# RPIcoffeeOptocouplerboard.net
KiCad netlist of a schematic drawn in EAGLE
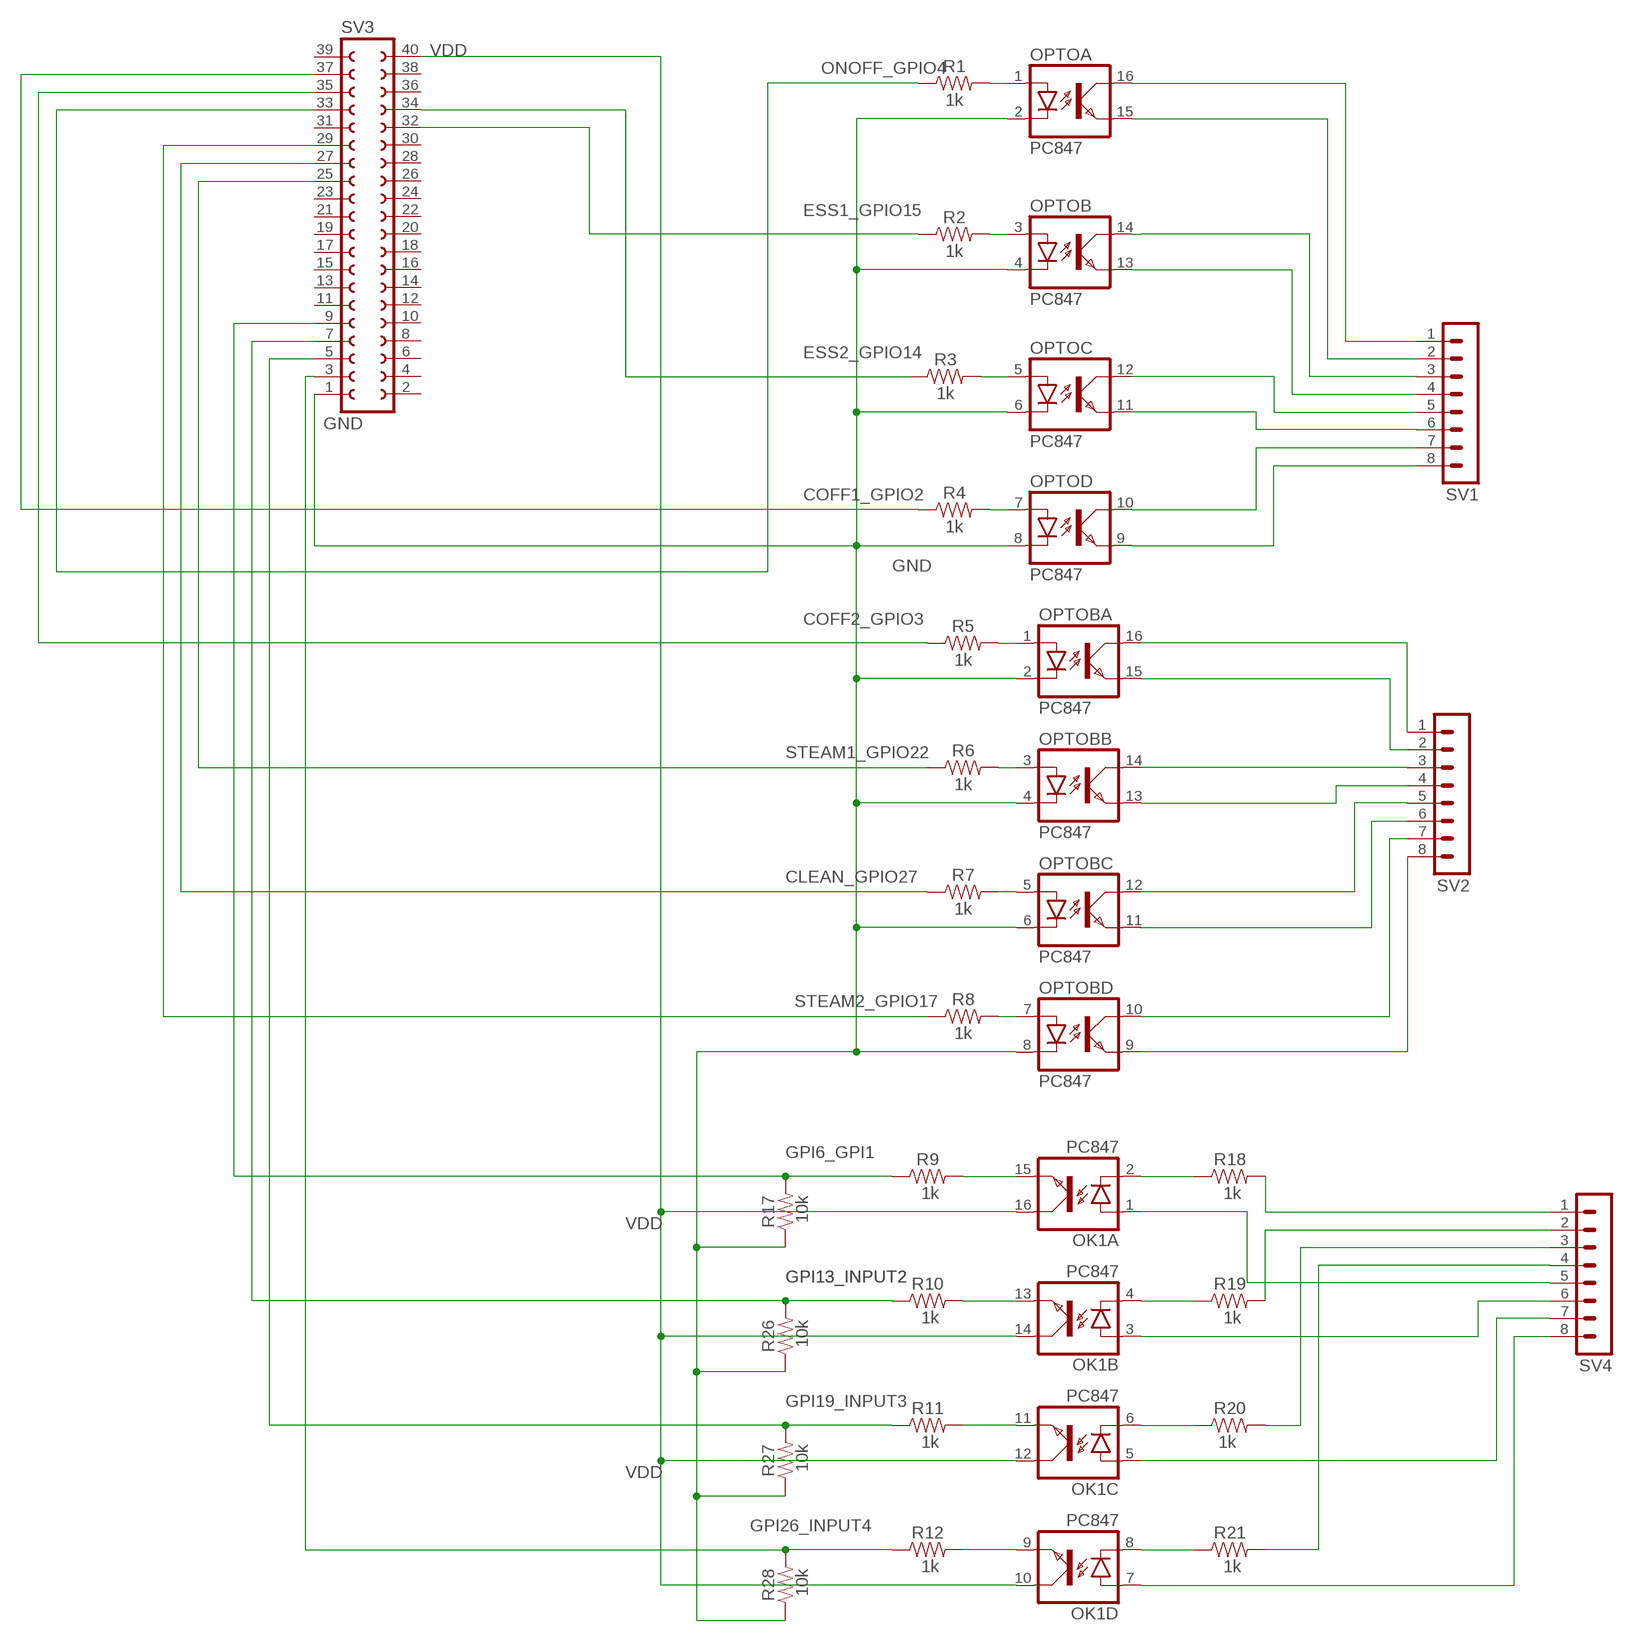
[diagram p0: schematic, sheet 1]

(export (version "E")
  (design (tool "Eeschema 10.0.6"))
  (components
    (comp (ref "OK1")
      (value "PC847")
      (footprint "eagle-import:DIL16")
      (libsource (lib "eagle-import") (part "PC847"))
    )
    (comp (ref "OPTO")
      (value "PC847")
      (footprint "eagle-import:DIL16")
      (libsource (lib "eagle-import") (part "PC847"))
    )
    (comp (ref "OPTOB")
      (value "PC847")
      (footprint "eagle-import:DIL16")
      (libsource (lib "eagle-import") (part "PC847"))
    )
    (comp (ref "R1")
      (value "1k")
      (footprint "eagle-import:AXIAL-0.3")
      (libsource (lib "eagle-import") (part "1KOHM-HORIZ-1/4W-5%"))
    )
    (comp (ref "R2")
      (value "1k")
      (footprint "eagle-import:AXIAL-0.3")
      (libsource (lib "eagle-import") (part "1KOHM-HORIZ-1/4W-5%"))
    )
    (comp (ref "R3")
      (value "1k")
      (footprint "eagle-import:AXIAL-0.3")
      (libsource (lib "eagle-import") (part "1KOHM-HORIZ-1/4W-5%"))
    )
    (comp (ref "R4")
      (value "1k")
      (footprint "eagle-import:AXIAL-0.3")
      (libsource (lib "eagle-import") (part "1KOHM-HORIZ-1/4W-5%"))
    )
    (comp (ref "R5")
      (value "1k")
      (footprint "eagle-import:AXIAL-0.3")
      (libsource (lib "eagle-import") (part "1KOHM-HORIZ-1/4W-5%"))
    )
    (comp (ref "R6")
      (value "1k")
      (footprint "eagle-import:AXIAL-0.3")
      (libsource (lib "eagle-import") (part "1KOHM-HORIZ-1/4W-5%"))
    )
    (comp (ref "R7")
      (value "1k")
      (footprint "eagle-import:AXIAL-0.3")
      (libsource (lib "eagle-import") (part "1KOHM-HORIZ-1/4W-5%"))
    )
    (comp (ref "R8")
      (value "1k")
      (footprint "eagle-import:AXIAL-0.3")
      (libsource (lib "eagle-import") (part "1KOHM-HORIZ-1/4W-5%"))
    )
    (comp (ref "R9")
      (value "1k")
      (footprint "eagle-import:AXIAL-0.3")
      (libsource (lib "eagle-import") (part "RESISTORAXIAL-0.3"))
    )
    (comp (ref "R10")
      (value "1k")
      (footprint "eagle-import:AXIAL-0.3")
      (libsource (lib "eagle-import") (part "RESISTORAXIAL-0.3"))
    )
    (comp (ref "R11")
      (value "1k")
      (footprint "eagle-import:AXIAL-0.3")
      (libsource (lib "eagle-import") (part "RESISTORAXIAL-0.3"))
    )
    (comp (ref "R12")
      (value "1k")
      (footprint "eagle-import:AXIAL-0.3")
      (libsource (lib "eagle-import") (part "RESISTORAXIAL-0.3"))
    )
    (comp (ref "R17")
      (value "10k")
      (footprint "eagle-import:AXIAL-0.3")
      (libsource (lib "eagle-import") (part "RESISTORAXIAL-0.3"))
    )
    (comp (ref "R18")
      (value "1k")
      (footprint "eagle-import:AXIAL-0.3")
      (libsource (lib "eagle-import") (part "RESISTORAXIAL-0.3"))
    )
    (comp (ref "R19")
      (value "1k")
      (footprint "eagle-import:AXIAL-0.3")
      (libsource (lib "eagle-import") (part "RESISTORAXIAL-0.3"))
    )
    (comp (ref "R20")
      (value "1k")
      (footprint "eagle-import:AXIAL-0.3")
      (libsource (lib "eagle-import") (part "RESISTORAXIAL-0.3"))
    )
    (comp (ref "R21")
      (value "1k")
      (footprint "eagle-import:AXIAL-0.3")
      (libsource (lib "eagle-import") (part "RESISTORAXIAL-0.3"))
    )
    (comp (ref "R26")
      (value "10k")
      (footprint "eagle-import:AXIAL-0.3")
      (libsource (lib "eagle-import") (part "RESISTORAXIAL-0.3"))
    )
    (comp (ref "R27")
      (value "10k")
      (footprint "eagle-import:AXIAL-0.3")
      (libsource (lib "eagle-import") (part "RESISTORAXIAL-0.3"))
    )
    (comp (ref "R28")
      (value "10k")
      (footprint "eagle-import:AXIAL-0.3")
      (libsource (lib "eagle-import") (part "RESISTORAXIAL-0.3"))
    )
    (comp (ref "SV1")
      (value "MA08-1")
      (footprint "eagle-import:MA08-1")
      (libsource (lib "eagle-import") (part "MA08-1"))
    )
    (comp (ref "SV2")
      (value "MA08-1")
      (footprint "eagle-import:MA08-1")
      (libsource (lib "eagle-import") (part "MA08-1"))
    )
    (comp (ref "SV3")
      (value "FE20-2")
      (footprint "eagle-import:FE20-2")
      (libsource (lib "eagle-import") (part "FE20-2"))
    )
    (comp (ref "SV4")
      (value "MA08-1")
      (footprint "eagle-import:MA08-1")
      (libsource (lib "eagle-import") (part "MA08-1"))
    )
  )
  (nets
    (net (code "1") (name "/CLEAN_GPIO27") (class "Default")
      (node (ref "R7") (pin "P$1") (pinfunction "1_P$1") (pintype "passive"))
      (node (ref "SV3") (pin "27") (pinfunction "27_27") (pintype "passive"))
    )
    (net (code "2") (name "/COFF1_GPIO2") (class "Default")
      (node (ref "R4") (pin "P$1") (pinfunction "1_P$1") (pintype "passive"))
      (node (ref "SV3") (pin "37") (pinfunction "37_37") (pintype "passive"))
    )
    (net (code "3") (name "/COFF2_GPIO3") (class "Default")
      (node (ref "R5") (pin "P$1") (pinfunction "1_P$1") (pintype "passive"))
      (node (ref "SV3") (pin "35") (pinfunction "35_35") (pintype "passive"))
    )
    (net (code "4") (name "/ESS1_GPIO15") (class "Default")
      (node (ref "R2") (pin "P$1") (pinfunction "1_P$1") (pintype "passive"))
      (node (ref "SV3") (pin "32") (pinfunction "32_32") (pintype "passive"))
    )
    (net (code "5") (name "/ESS2_GPIO14") (class "Default")
      (node (ref "R3") (pin "P$1") (pinfunction "1_P$1") (pintype "passive"))
      (node (ref "SV3") (pin "34") (pinfunction "34_34") (pintype "passive"))
    )
    (net (code "6") (name "/GND") (class "Default")
      (node (ref "OPTO") (pin "2") (pinfunction "C_2") (pintype "passive"))
      (node (ref "OPTO") (pin "4") (pinfunction "C_4") (pintype "passive"))
      (node (ref "OPTO") (pin "6") (pinfunction "C_6") (pintype "passive"))
      (node (ref "OPTO") (pin "8") (pinfunction "C_8") (pintype "passive"))
      (node (ref "OPTOB") (pin "2") (pinfunction "C_2") (pintype "passive"))
      (node (ref "OPTOB") (pin "4") (pinfunction "C_4") (pintype "passive"))
      (node (ref "OPTOB") (pin "6") (pinfunction "C_6") (pintype "passive"))
      (node (ref "OPTOB") (pin "8") (pinfunction "C_8") (pintype "passive"))
      (node (ref "R17") (pin "P$1") (pinfunction "1_P$1") (pintype "passive"))
      (node (ref "R26") (pin "P$1") (pinfunction "1_P$1") (pintype "passive"))
      (node (ref "R27") (pin "P$1") (pinfunction "1_P$1") (pintype "passive"))
      (node (ref "R28") (pin "P$1") (pinfunction "1_P$1") (pintype "passive"))
      (node (ref "SV3") (pin "1") (pinfunction "1_1") (pintype "passive"))
    )
    (net (code "7") (name "/GPI6_GPI1") (class "Default")
      (node (ref "R17") (pin "P$2") (pinfunction "2_P$2") (pintype "passive"))
      (node (ref "R9") (pin "P$1") (pinfunction "1_P$1") (pintype "passive"))
      (node (ref "SV3") (pin "9") (pinfunction "9_9") (pintype "passive"))
    )
    (net (code "8") (name "/GPI13_INPUT2") (class "Default")
      (node (ref "R10") (pin "P$1") (pinfunction "1_P$1") (pintype "passive"))
      (node (ref "R26") (pin "P$2") (pinfunction "2_P$2") (pintype "passive"))
      (node (ref "SV3") (pin "7") (pinfunction "7_7") (pintype "passive"))
    )
    (net (code "9") (name "/GPI19_INPUT3") (class "Default")
      (node (ref "R11") (pin "P$1") (pinfunction "1_P$1") (pintype "passive"))
      (node (ref "R27") (pin "P$2") (pinfunction "2_P$2") (pintype "passive"))
      (node (ref "SV3") (pin "5") (pinfunction "5_5") (pintype "passive"))
    )
    (net (code "10") (name "/GPI26_INPUT4") (class "Default")
      (node (ref "R12") (pin "P$1") (pinfunction "1_P$1") (pintype "passive"))
      (node (ref "R28") (pin "P$2") (pinfunction "2_P$2") (pintype "passive"))
      (node (ref "SV3") (pin "3") (pinfunction "3_3") (pintype "passive"))
    )
    (net (code "11") (name "/ONOFF_GPIO4") (class "Default")
      (node (ref "R1") (pin "P$1") (pinfunction "1_P$1") (pintype "passive"))
      (node (ref "SV3") (pin "33") (pinfunction "33_33") (pintype "passive"))
    )
    (net (code "12") (name "/STEAM1_GPIO22") (class "Default")
      (node (ref "R6") (pin "P$1") (pinfunction "1_P$1") (pintype "passive"))
      (node (ref "SV3") (pin "25") (pinfunction "25_25") (pintype "passive"))
    )
    (net (code "13") (name "/STEAM2_GPIO17") (class "Default")
      (node (ref "R8") (pin "P$1") (pinfunction "1_P$1") (pintype "passive"))
      (node (ref "SV3") (pin "29") (pinfunction "29_29") (pintype "passive"))
    )
    (net (code "14") (name "/VDD") (class "Default")
      (node (ref "OK1") (pin "10") (pinfunction "COL_10") (pintype "passive"))
      (node (ref "OK1") (pin "12") (pinfunction "COL_12") (pintype "passive"))
      (node (ref "OK1") (pin "14") (pinfunction "COL_14") (pintype "passive"))
      (node (ref "OK1") (pin "16") (pinfunction "COL_16") (pintype "passive"))
      (node (ref "SV3") (pin "40") (pinfunction "40_40") (pintype "passive"))
    )
    (net (code "15") (name "Net-(OK1A-A)") (class "Default")
      (node (ref "OK1") (pin "1") (pinfunction "A_1") (pintype "passive"))
      (node (ref "SV4") (pin "5") (pinfunction "5_5") (pintype "passive"))
    )
    (net (code "16") (name "Net-(OK1A-C)") (class "Default")
      (node (ref "OK1") (pin "2") (pinfunction "C_2") (pintype "passive"))
      (node (ref "R18") (pin "P$1") (pinfunction "1_P$1") (pintype "passive"))
    )
    (net (code "17") (name "Net-(OK1A-EMIT)") (class "Default")
      (node (ref "OK1") (pin "15") (pinfunction "EMIT_15") (pintype "passive"))
      (node (ref "R9") (pin "P$2") (pinfunction "2_P$2") (pintype "passive"))
    )
    (net (code "18") (name "Net-(OK1B-A)") (class "Default")
      (node (ref "OK1") (pin "3") (pinfunction "A_3") (pintype "passive"))
      (node (ref "SV4") (pin "6") (pinfunction "6_6") (pintype "passive"))
    )
    (net (code "19") (name "Net-(OK1B-C)") (class "Default")
      (node (ref "OK1") (pin "4") (pinfunction "C_4") (pintype "passive"))
      (node (ref "R19") (pin "P$1") (pinfunction "1_P$1") (pintype "passive"))
    )
    (net (code "20") (name "Net-(OK1B-EMIT)") (class "Default")
      (node (ref "OK1") (pin "13") (pinfunction "EMIT_13") (pintype "passive"))
      (node (ref "R10") (pin "P$2") (pinfunction "2_P$2") (pintype "passive"))
    )
    (net (code "21") (name "Net-(OK1C-A)") (class "Default")
      (node (ref "OK1") (pin "5") (pinfunction "A_5") (pintype "passive"))
      (node (ref "SV4") (pin "7") (pinfunction "7_7") (pintype "passive"))
    )
    (net (code "22") (name "Net-(OK1C-C)") (class "Default")
      (node (ref "OK1") (pin "6") (pinfunction "C_6") (pintype "passive"))
      (node (ref "R20") (pin "P$1") (pinfunction "1_P$1") (pintype "passive"))
    )
    (net (code "23") (name "Net-(OK1C-EMIT)") (class "Default")
      (node (ref "OK1") (pin "11") (pinfunction "EMIT_11") (pintype "passive"))
      (node (ref "R11") (pin "P$2") (pinfunction "2_P$2") (pintype "passive"))
    )
    (net (code "24") (name "Net-(OK1D-A)") (class "Default")
      (node (ref "OK1") (pin "7") (pinfunction "A_7") (pintype "passive"))
      (node (ref "SV4") (pin "8") (pinfunction "8_8") (pintype "passive"))
    )
    (net (code "25") (name "Net-(OK1D-C)") (class "Default")
      (node (ref "OK1") (pin "8") (pinfunction "C_8") (pintype "passive"))
      (node (ref "R21") (pin "P$1") (pinfunction "1_P$1") (pintype "passive"))
    )
    (net (code "26") (name "Net-(OK1D-EMIT)") (class "Default")
      (node (ref "OK1") (pin "9") (pinfunction "EMIT_9") (pintype "passive"))
      (node (ref "R12") (pin "P$2") (pinfunction "2_P$2") (pintype "passive"))
    )
    (net (code "27") (name "Net-(OPTOA-A)") (class "Default")
      (node (ref "OPTO") (pin "1") (pinfunction "A_1") (pintype "passive"))
      (node (ref "R1") (pin "P$2") (pinfunction "2_P$2") (pintype "passive"))
    )
    (net (code "28") (name "Net-(OPTOA-COL)") (class "Default")
      (node (ref "OPTO") (pin "16") (pinfunction "COL_16") (pintype "passive"))
      (node (ref "SV1") (pin "1") (pinfunction "1_1") (pintype "passive"))
    )
    (net (code "29") (name "Net-(OPTOA-EMIT)") (class "Default")
      (node (ref "OPTO") (pin "15") (pinfunction "EMIT_15") (pintype "passive"))
      (node (ref "SV1") (pin "2") (pinfunction "2_2") (pintype "passive"))
    )
    (net (code "30") (name "Net-(OPTOB-A)") (class "Default")
      (node (ref "OPTO") (pin "3") (pinfunction "A_3") (pintype "passive"))
      (node (ref "R2") (pin "P$2") (pinfunction "2_P$2") (pintype "passive"))
    )
    (net (code "31") (name "Net-(OPTOB-COL)") (class "Default")
      (node (ref "OPTO") (pin "14") (pinfunction "COL_14") (pintype "passive"))
      (node (ref "SV1") (pin "3") (pinfunction "3_3") (pintype "passive"))
    )
    (net (code "32") (name "Net-(OPTOB-EMIT)") (class "Default")
      (node (ref "OPTO") (pin "13") (pinfunction "EMIT_13") (pintype "passive"))
      (node (ref "SV1") (pin "4") (pinfunction "4_4") (pintype "passive"))
    )
    (net (code "33") (name "Net-(OPTOBA-A)") (class "Default")
      (node (ref "OPTOB") (pin "1") (pinfunction "A_1") (pintype "passive"))
      (node (ref "R5") (pin "P$2") (pinfunction "2_P$2") (pintype "passive"))
    )
    (net (code "34") (name "Net-(OPTOBA-COL)") (class "Default")
      (node (ref "OPTOB") (pin "16") (pinfunction "COL_16") (pintype "passive"))
      (node (ref "SV2") (pin "1") (pinfunction "1_1") (pintype "passive"))
    )
    (net (code "35") (name "Net-(OPTOBA-EMIT)") (class "Default")
      (node (ref "OPTOB") (pin "15") (pinfunction "EMIT_15") (pintype "passive"))
      (node (ref "SV2") (pin "2") (pinfunction "2_2") (pintype "passive"))
    )
    (net (code "36") (name "Net-(OPTOBB-A)") (class "Default")
      (node (ref "OPTOB") (pin "3") (pinfunction "A_3") (pintype "passive"))
      (node (ref "R6") (pin "P$2") (pinfunction "2_P$2") (pintype "passive"))
    )
    (net (code "37") (name "Net-(OPTOBB-COL)") (class "Default")
      (node (ref "OPTOB") (pin "14") (pinfunction "COL_14") (pintype "passive"))
      (node (ref "SV2") (pin "3") (pinfunction "3_3") (pintype "passive"))
    )
    (net (code "38") (name "Net-(OPTOBB-EMIT)") (class "Default")
      (node (ref "OPTOB") (pin "13") (pinfunction "EMIT_13") (pintype "passive"))
      (node (ref "SV2") (pin "4") (pinfunction "4_4") (pintype "passive"))
    )
    (net (code "39") (name "Net-(OPTOBC-A)") (class "Default")
      (node (ref "OPTOB") (pin "5") (pinfunction "A_5") (pintype "passive"))
      (node (ref "R7") (pin "P$2") (pinfunction "2_P$2") (pintype "passive"))
    )
    (net (code "40") (name "Net-(OPTOBC-COL)") (class "Default")
      (node (ref "OPTOB") (pin "12") (pinfunction "COL_12") (pintype "passive"))
      (node (ref "SV2") (pin "5") (pinfunction "5_5") (pintype "passive"))
    )
    (net (code "41") (name "Net-(OPTOBC-EMIT)") (class "Default")
      (node (ref "OPTOB") (pin "11") (pinfunction "EMIT_11") (pintype "passive"))
      (node (ref "SV2") (pin "6") (pinfunction "6_6") (pintype "passive"))
    )
    (net (code "42") (name "Net-(OPTOBD-A)") (class "Default")
      (node (ref "OPTOB") (pin "7") (pinfunction "A_7") (pintype "passive"))
      (node (ref "R8") (pin "P$2") (pinfunction "2_P$2") (pintype "passive"))
    )
    (net (code "43") (name "Net-(OPTOBD-COL)") (class "Default")
      (node (ref "OPTOB") (pin "10") (pinfunction "COL_10") (pintype "passive"))
      (node (ref "SV2") (pin "7") (pinfunction "7_7") (pintype "passive"))
    )
    (net (code "44") (name "Net-(OPTOBD-EMIT)") (class "Default")
      (node (ref "OPTOB") (pin "9") (pinfunction "EMIT_9") (pintype "passive"))
      (node (ref "SV2") (pin "8") (pinfunction "8_8") (pintype "passive"))
    )
    (net (code "45") (name "Net-(OPTOC-A)") (class "Default")
      (node (ref "OPTO") (pin "5") (pinfunction "A_5") (pintype "passive"))
      (node (ref "R3") (pin "P$2") (pinfunction "2_P$2") (pintype "passive"))
    )
    (net (code "46") (name "Net-(OPTOC-COL)") (class "Default")
      (node (ref "OPTO") (pin "12") (pinfunction "COL_12") (pintype "passive"))
      (node (ref "SV1") (pin "5") (pinfunction "5_5") (pintype "passive"))
    )
    (net (code "47") (name "Net-(OPTOC-EMIT)") (class "Default")
      (node (ref "OPTO") (pin "11") (pinfunction "EMIT_11") (pintype "passive"))
      (node (ref "SV1") (pin "6") (pinfunction "6_6") (pintype "passive"))
    )
    (net (code "48") (name "Net-(OPTOD-A)") (class "Default")
      (node (ref "OPTO") (pin "7") (pinfunction "A_7") (pintype "passive"))
      (node (ref "R4") (pin "P$2") (pinfunction "2_P$2") (pintype "passive"))
    )
    (net (code "49") (name "Net-(OPTOD-COL)") (class "Default")
      (node (ref "OPTO") (pin "10") (pinfunction "COL_10") (pintype "passive"))
      (node (ref "SV1") (pin "7") (pinfunction "7_7") (pintype "passive"))
    )
    (net (code "50") (name "Net-(OPTOD-EMIT)") (class "Default")
      (node (ref "OPTO") (pin "9") (pinfunction "EMIT_9") (pintype "passive"))
      (node (ref "SV1") (pin "8") (pinfunction "8_8") (pintype "passive"))
    )
    (net (code "51") (name "Net-(R18-2)") (class "Default")
      (node (ref "R18") (pin "P$2") (pinfunction "2_P$2") (pintype "passive"))
      (node (ref "SV4") (pin "1") (pinfunction "1_1") (pintype "passive"))
    )
    (net (code "52") (name "Net-(R19-2)") (class "Default")
      (node (ref "R19") (pin "P$2") (pinfunction "2_P$2") (pintype "passive"))
      (node (ref "SV4") (pin "2") (pinfunction "2_2") (pintype "passive"))
    )
    (net (code "53") (name "Net-(R20-2)") (class "Default")
      (node (ref "R20") (pin "P$2") (pinfunction "2_P$2") (pintype "passive"))
      (node (ref "SV4") (pin "3") (pinfunction "3_3") (pintype "passive"))
    )
    (net (code "54") (name "Net-(R21-2)") (class "Default")
      (node (ref "R21") (pin "P$2") (pinfunction "2_P$2") (pintype "passive"))
      (node (ref "SV4") (pin "4") (pinfunction "4_4") (pintype "passive"))
    )
    (net (code "55") (name "unconnected-(SV3-Pad2)") (class "Default")
      (node (ref "SV3") (pin "2") (pinfunction "2_2") (pintype "passive"))
    )
    (net (code "56") (name "unconnected-(SV3-Pad4)") (class "Default")
      (node (ref "SV3") (pin "4") (pinfunction "4_4") (pintype "passive"))
    )
    (net (code "57") (name "unconnected-(SV3-Pad6)") (class "Default")
      (node (ref "SV3") (pin "6") (pinfunction "6_6") (pintype "passive"))
    )
    (net (code "58") (name "unconnected-(SV3-Pad8)") (class "Default")
      (node (ref "SV3") (pin "8") (pinfunction "8_8") (pintype "passive"))
    )
    (net (code "59") (name "unconnected-(SV3-Pad10)") (class "Default")
      (node (ref "SV3") (pin "10") (pinfunction "10_10") (pintype "passive"))
    )
    (net (code "60") (name "unconnected-(SV3-Pad11)") (class "Default")
      (node (ref "SV3") (pin "11") (pinfunction "11_11") (pintype "passive"))
    )
    (net (code "61") (name "unconnected-(SV3-Pad12)") (class "Default")
      (node (ref "SV3") (pin "12") (pinfunction "12_12") (pintype "passive"))
    )
    (net (code "62") (name "unconnected-(SV3-Pad13)") (class "Default")
      (node (ref "SV3") (pin "13") (pinfunction "13_13") (pintype "passive"))
    )
    (net (code "63") (name "unconnected-(SV3-Pad14)") (class "Default")
      (node (ref "SV3") (pin "14") (pinfunction "14_14") (pintype "passive"))
    )
    (net (code "64") (name "unconnected-(SV3-Pad15)") (class "Default")
      (node (ref "SV3") (pin "15") (pinfunction "15_15") (pintype "passive"))
    )
    (net (code "65") (name "unconnected-(SV3-Pad16)") (class "Default")
      (node (ref "SV3") (pin "16") (pinfunction "16_16") (pintype "passive"))
    )
    (net (code "66") (name "unconnected-(SV3-Pad17)") (class "Default")
      (node (ref "SV3") (pin "17") (pinfunction "17_17") (pintype "passive"))
    )
    (net (code "67") (name "unconnected-(SV3-Pad18)") (class "Default")
      (node (ref "SV3") (pin "18") (pinfunction "18_18") (pintype "passive"))
    )
    (net (code "68") (name "unconnected-(SV3-Pad19)") (class "Default")
      (node (ref "SV3") (pin "19") (pinfunction "19_19") (pintype "passive"))
    )
    (net (code "69") (name "unconnected-(SV3-Pad20)") (class "Default")
      (node (ref "SV3") (pin "20") (pinfunction "20_20") (pintype "passive"))
    )
    (net (code "70") (name "unconnected-(SV3-Pad21)") (class "Default")
      (node (ref "SV3") (pin "21") (pinfunction "21_21") (pintype "passive"))
    )
    (net (code "71") (name "unconnected-(SV3-Pad22)") (class "Default")
      (node (ref "SV3") (pin "22") (pinfunction "22_22") (pintype "passive"))
    )
    (net (code "72") (name "unconnected-(SV3-Pad23)") (class "Default")
      (node (ref "SV3") (pin "23") (pinfunction "23_23") (pintype "passive"))
    )
    (net (code "73") (name "unconnected-(SV3-Pad24)") (class "Default")
      (node (ref "SV3") (pin "24") (pinfunction "24_24") (pintype "passive"))
    )
    (net (code "74") (name "unconnected-(SV3-Pad26)") (class "Default")
      (node (ref "SV3") (pin "26") (pinfunction "26_26") (pintype "passive"))
    )
    (net (code "75") (name "unconnected-(SV3-Pad28)") (class "Default")
      (node (ref "SV3") (pin "28") (pinfunction "28_28") (pintype "passive"))
    )
    (net (code "76") (name "unconnected-(SV3-Pad30)") (class "Default")
      (node (ref "SV3") (pin "30") (pinfunction "30_30") (pintype "passive"))
    )
    (net (code "77") (name "unconnected-(SV3-Pad31)") (class "Default")
      (node (ref "SV3") (pin "31") (pinfunction "31_31") (pintype "passive"))
    )
    (net (code "78") (name "unconnected-(SV3-Pad36)") (class "Default")
      (node (ref "SV3") (pin "36") (pinfunction "36_36") (pintype "passive"))
    )
    (net (code "79") (name "unconnected-(SV3-Pad38)") (class "Default")
      (node (ref "SV3") (pin "38") (pinfunction "38_38") (pintype "passive"))
    )
    (net (code "80") (name "unconnected-(SV3-Pad39)") (class "Default")
      (node (ref "SV3") (pin "39") (pinfunction "39_39") (pintype "passive"))
    )
  )
)
